# CPU.net
KiCad netlist of a schematic drawn in Altium Designer
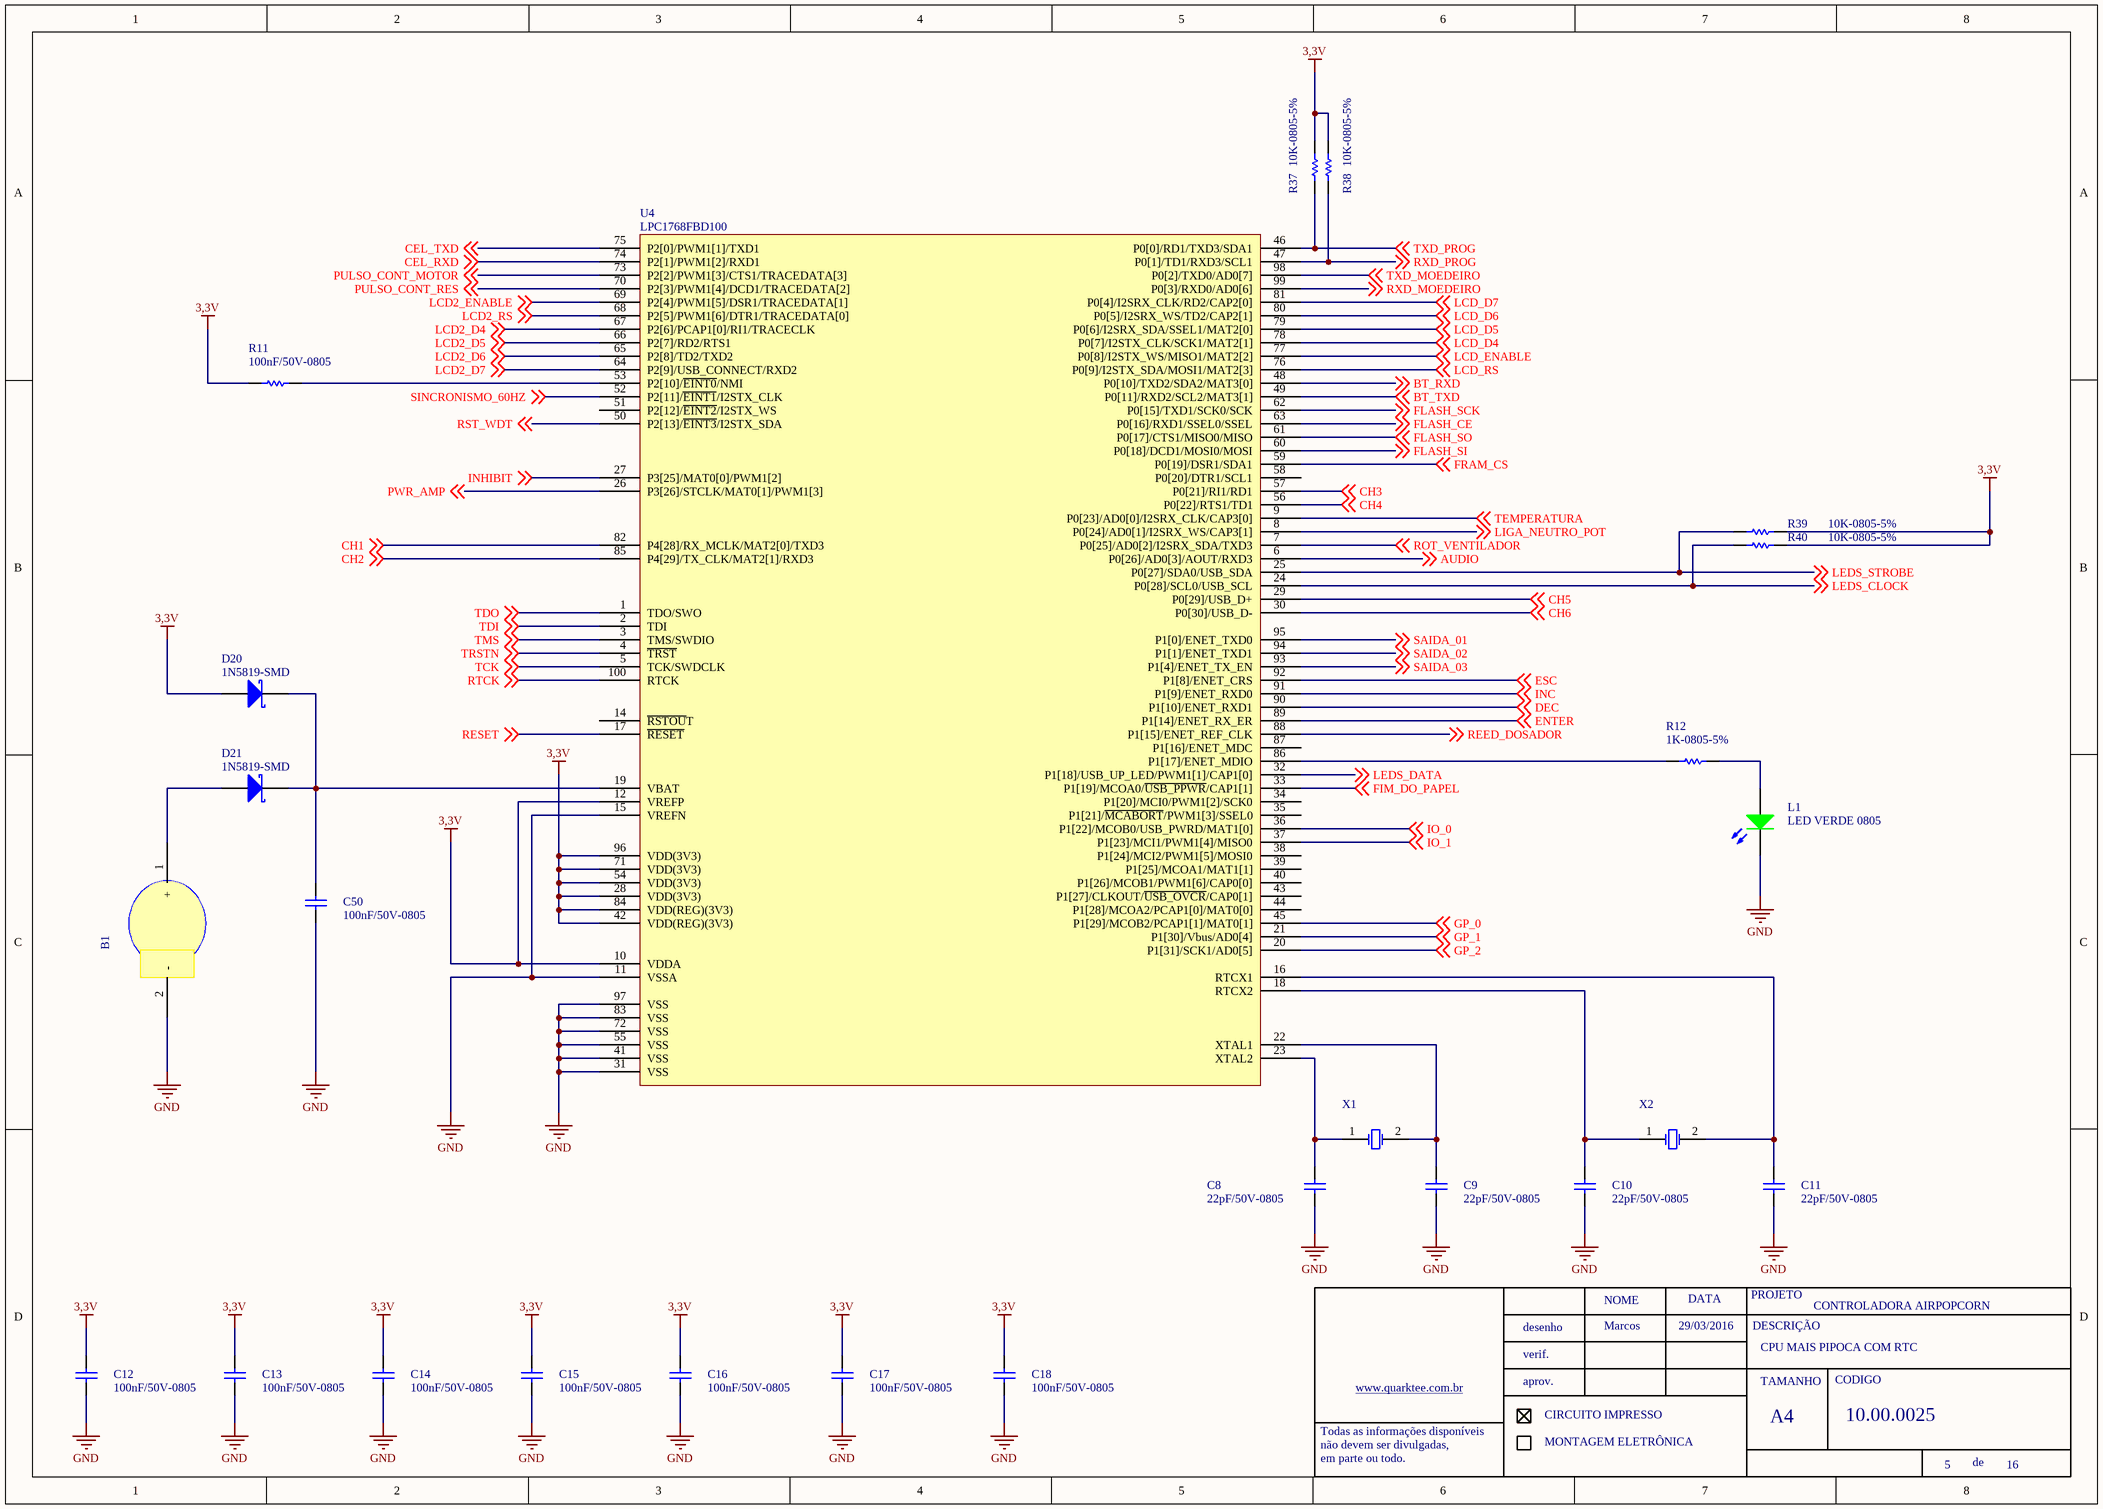
[diagram p0: CPU.SchDoc]

(export (version "E")
  (design (tool "Eeschema 10.0.6"))
  (components
    (comp (ref "B1")
      (value "~")
      (description "SUPORTE PILHA CR2032")
      (libsource (lib "ChaveDigital3") (part "SUPORTE PILHA CR2032"))
    )
    (comp (ref "C8")
      (value "22pF/50V-0805")
      (footprint "0805-REVISADO O")
      (description "22pF-0805-NPO")
      (libsource (lib "AquinoLib") (part "22pF-0805-NPO"))
    )
    (comp (ref "C9")
      (value "22pF/50V-0805")
      (footprint "0805-REVISADO O")
      (description "22pF-0805-NPO")
      (libsource (lib "AquinoLib") (part "22pF-0805-NPO"))
    )
    (comp (ref "C10")
      (value "22pF/50V-0805")
      (footprint "0805-REVISADO O")
      (description "22pF-0805-NPO")
      (libsource (lib "AquinoLib") (part "22pF-0805-NPO"))
    )
    (comp (ref "C11")
      (value "22pF/50V-0805")
      (footprint "0805-REVISADO O")
      (description "22pF-0805-NPO")
      (libsource (lib "AquinoLib") (part "22pF-0805-NPO"))
    )
    (comp (ref "C12")
      (value "100nF/50V-0805")
      (footprint "0805-REVISADO O")
      (description "100nF/50-0805-NPO")
      (libsource (lib "AquinoLib") (part "100nF/50-0805-NPO"))
    )
    (comp (ref "C13")
      (value "100nF/50V-0805")
      (footprint "0805-REVISADO O")
      (description "100nF/50-0805-NPO")
      (libsource (lib "AquinoLib") (part "100nF/50-0805-NPO"))
    )
    (comp (ref "C14")
      (value "100nF/50V-0805")
      (footprint "0805-REVISADO O")
      (description "100nF/50-0805-NPO")
      (libsource (lib "AquinoLib") (part "100nF/50-0805-NPO"))
    )
    (comp (ref "C15")
      (value "100nF/50V-0805")
      (footprint "0805-REVISADO O")
      (description "100nF/50-0805-NPO")
      (libsource (lib "AquinoLib") (part "100nF/50-0805-NPO"))
    )
    (comp (ref "C16")
      (value "100nF/50V-0805")
      (footprint "0805-REVISADO O")
      (description "100nF/50-0805-NPO")
      (libsource (lib "AquinoLib") (part "100nF/50-0805-NPO"))
    )
    (comp (ref "C17")
      (value "100nF/50V-0805")
      (footprint "0805-REVISADO O")
      (description "100nF/50-0805-NPO")
      (libsource (lib "AquinoLib") (part "100nF/50-0805-NPO"))
    )
    (comp (ref "C18")
      (value "100nF/50V-0805")
      (footprint "0805-REVISADO O")
      (description "100nF/50-0805-NPO")
      (libsource (lib "AquinoLib") (part "100nF/50-0805-NPO"))
    )
    (comp (ref "C50")
      (value "100nF/50V-0805")
      (footprint "0805-REVISADO O")
      (description "100nF/50-0805-NPO")
      (libsource (lib "AquinoLib") (part "100nF/50-0805-NPO"))
    )
    (comp (ref "D20")
      (value "1N5819-SMD")
      (description "1N5819")
      (libsource (lib "ChaveDigital3") (part "1N5819"))
    )
    (comp (ref "D21")
      (value "1N5819-SMD")
      (description "1N5819")
      (libsource (lib "ChaveDigital3") (part "1N5819"))
    )
    (comp (ref "L1")
      (value "LED VERDE 0805")
      (footprint "LED 0805 - REVI")
      (description "LED VERDE 0603 VERDE")
      (libsource (lib "AquinoLib") (part "LED VERDE 0603 SMD"))
    )
    (comp (ref "R11")
      (value "100nF/50V-0805")
      (footprint "0805-REVISADO O")
      (description "10K-0805-5%")
      (libsource (lib "AquinoLib") (part "10K-0805-5%"))
    )
    (comp (ref "R12")
      (value "1K-0805-5%")
      (footprint "0805-REVISADO O")
      (libsource (lib "AquinoLib") (part "1K-0805-5%"))
    )
    (comp (ref "R37")
      (value "10K-0805-5%")
      (footprint "0805-REVISADO O")
      (libsource (lib "AquinoLib") (part "10K-0805-5%"))
    )
    (comp (ref "R38")
      (value "10K-0805-5%")
      (footprint "0805-REVISADO O")
      (libsource (lib "AquinoLib") (part "10K-0805-5%"))
    )
    (comp (ref "R39")
      (value "10K-0805-5%")
      (footprint "0805-REVISADO O")
      (libsource (lib "AquinoLib") (part "10K-0805-5%"))
    )
    (comp (ref "R40")
      (value "10K-0805-5%")
      (footprint "0805-REVISADO O")
      (libsource (lib "AquinoLib") (part "10K-0805-5%"))
    )
    (comp (ref "U4")
      (value "LPC1768FBD100")
      (footprint "LQFP-100 pasta")
      (libsource (lib "ChaveDigital3") (part "LPC1768FDB100"))
    )
    (comp (ref "X1")
      (value "~")
      (footprint "XTALV'")
      (description "12MHZ")
      (libsource (lib "AquinoLib") (part "CRISTAL 12MHZ"))
    )
    (comp (ref "X2")
      (value "~")
      (footprint "XTAL_32768'")
      (description "CRISTAL 32.768Hz")
      (libsource (lib "AquinoLib") (part "CRISTAL 32.768 Hz"))
    )
  )
  (nets
    (net (code "1") (name "3,3V") (class "Default")
      (node (ref "C12") (pin "2") (pinfunction "2_2") (pintype "passive"))
      (node (ref "C13") (pin "2") (pinfunction "2_2") (pintype "passive"))
      (node (ref "C14") (pin "2") (pinfunction "2_2") (pintype "passive"))
      (node (ref "C15") (pin "2") (pinfunction "2_2") (pintype "passive"))
      (node (ref "C16") (pin "2") (pinfunction "2_2") (pintype "passive"))
      (node (ref "C17") (pin "2") (pinfunction "2_2") (pintype "passive"))
      (node (ref "C18") (pin "2") (pinfunction "2_2") (pintype "passive"))
      (node (ref "D20") (pin "1") (pinfunction "A_1") (pintype "passive"))
      (node (ref "R11") (pin "1") (pinfunction "1_1") (pintype "passive"))
      (node (ref "R37") (pin "2") (pinfunction "2_2") (pintype "passive"))
      (node (ref "R38") (pin "2") (pinfunction "2_2") (pintype "passive"))
      (node (ref "R39") (pin "2") (pinfunction "2_2") (pintype "passive"))
      (node (ref "R40") (pin "2") (pinfunction "2_2") (pintype "passive"))
      (node (ref "U4") (pin "10") (pinfunction "VDDA_10") (pintype "passive"))
      (node (ref "U4") (pin "12") (pinfunction "VREFP_12") (pintype "passive"))
      (node (ref "U4") (pin "28") (pinfunction "VDD(3V3)_28") (pintype "passive"))
      (node (ref "U4") (pin "42") (pinfunction "VDD(REG)(3V3)_42") (pintype "passive"))
      (node (ref "U4") (pin "54") (pinfunction "VDD(3V3)_54") (pintype "passive"))
      (node (ref "U4") (pin "71") (pinfunction "VDD(3V3)_71") (pintype "passive"))
      (node (ref "U4") (pin "84") (pinfunction "VDD(REG)(3V3)_84") (pintype "passive"))
      (node (ref "U4") (pin "96") (pinfunction "VDD(3V3)_96") (pintype "passive"))
    )
    (net (code "2") (name "AUDIO") (class "Default")
      (node (ref "U4") (pin "6") (pinfunction "P0[26]/AD0[3]/AOUT/RXD3_6") (pintype "passive"))
    )
    (net (code "3") (name "BT_RXD") (class "Default")
      (node (ref "U4") (pin "48") (pinfunction "P0[10]/TXD2/SDA2/MAT3[0]_48") (pintype "passive"))
    )
    (net (code "4") (name "BT_TXD") (class "Default")
      (node (ref "U4") (pin "49") (pinfunction "P0[11]/RXD2/SCL2/MAT3[1]_49") (pintype "passive"))
    )
    (net (code "5") (name "CEL_RXD") (class "Default")
      (node (ref "U4") (pin "74") (pinfunction "P2[1]/PWM1[2]/RXD1_74") (pintype "passive"))
    )
    (net (code "6") (name "CEL_TXD") (class "Default")
      (node (ref "U4") (pin "75") (pinfunction "P2[0]/PWM1[1]/TXD1_75") (pintype "passive"))
    )
    (net (code "7") (name "CH1") (class "Default")
      (node (ref "U4") (pin "82") (pinfunction "P4[28]/RX_MCLK/MAT2[0]/TXD3_82") (pintype "passive"))
    )
    (net (code "8") (name "CH2") (class "Default")
      (node (ref "U4") (pin "85") (pinfunction "P4[29]/TX_CLK/MAT2[1]/RXD3_85") (pintype "passive"))
    )
    (net (code "9") (name "CH3") (class "Default")
      (node (ref "U4") (pin "57") (pinfunction "P0[21]/RI1/RD1_57") (pintype "passive"))
    )
    (net (code "10") (name "CH4") (class "Default")
      (node (ref "U4") (pin "56") (pinfunction "P0[22]/RTS1/TD1_56") (pintype "passive"))
    )
    (net (code "11") (name "CH5") (class "Default")
      (node (ref "U4") (pin "29") (pinfunction "P0[29]/USB_D+_29") (pintype "passive"))
    )
    (net (code "12") (name "CH6") (class "Default")
      (node (ref "U4") (pin "30") (pinfunction "P0[30]/USB_D-_30") (pintype "passive"))
    )
    (net (code "13") (name "DEC") (class "Default")
      (node (ref "U4") (pin "90") (pinfunction "P1[10]/ENET_RXD1_90") (pintype "passive"))
    )
    (net (code "14") (name "ENTER") (class "Default")
      (node (ref "U4") (pin "89") (pinfunction "P1[14]/ENET_RX_ER_89") (pintype "passive"))
    )
    (net (code "15") (name "ESC") (class "Default")
      (node (ref "U4") (pin "92") (pinfunction "P1[8]/ENET_CRS_92") (pintype "passive"))
    )
    (net (code "16") (name "FIM_DO_PAPEL") (class "Default")
      (node (ref "U4") (pin "33") (pinfunction "P1[19]/MCOA0/~{USB_PPWR}/CAP1[1]_33") (pintype "passive"))
    )
    (net (code "17") (name "FLASH_CE") (class "Default")
      (node (ref "U4") (pin "63") (pinfunction "P0[16]/RXD1/SSEL0/SSEL_63") (pintype "passive"))
    )
    (net (code "18") (name "FLASH_SCK") (class "Default")
      (node (ref "U4") (pin "62") (pinfunction "P0[15]/TXD1/SCK0/SCK_62") (pintype "passive"))
    )
    (net (code "19") (name "FLASH_SI") (class "Default")
      (node (ref "U4") (pin "60") (pinfunction "P0[18]/DCD1/MOSI0/MOSI_60") (pintype "passive"))
    )
    (net (code "20") (name "FLASH_SO") (class "Default")
      (node (ref "U4") (pin "61") (pinfunction "P0[17]/CTS1/MISO0/MISO_61") (pintype "passive"))
    )
    (net (code "21") (name "FRAM_CS") (class "Default")
      (node (ref "U4") (pin "59") (pinfunction "P0[19]/DSR1/SDA1_59") (pintype "passive"))
    )
    (net (code "22") (name "GND") (class "Default")
      (node (ref "B1") (pin "2") (pinfunction "-_2") (pintype "passive"))
      (node (ref "C10") (pin "1") (pinfunction "1_1") (pintype "passive"))
      (node (ref "C11") (pin "1") (pinfunction "1_1") (pintype "passive"))
      (node (ref "C12") (pin "1") (pinfunction "1_1") (pintype "passive"))
      (node (ref "C13") (pin "1") (pinfunction "1_1") (pintype "passive"))
      (node (ref "C14") (pin "1") (pinfunction "1_1") (pintype "passive"))
      (node (ref "C15") (pin "1") (pinfunction "1_1") (pintype "passive"))
      (node (ref "C16") (pin "1") (pinfunction "1_1") (pintype "passive"))
      (node (ref "C17") (pin "1") (pinfunction "1_1") (pintype "passive"))
      (node (ref "C18") (pin "1") (pinfunction "1_1") (pintype "passive"))
      (node (ref "C50") (pin "1") (pinfunction "1_1") (pintype "passive"))
      (node (ref "C8") (pin "1") (pinfunction "1_1") (pintype "passive"))
      (node (ref "C9") (pin "1") (pinfunction "1_1") (pintype "passive"))
      (node (ref "L1") (pin "2") (pinfunction "K_2") (pintype "passive"))
      (node (ref "U4") (pin "11") (pinfunction "VSSA_11") (pintype "passive"))
      (node (ref "U4") (pin "15") (pinfunction "VREFN_15") (pintype "passive"))
      (node (ref "U4") (pin "31") (pinfunction "VSS_31") (pintype "passive"))
      (node (ref "U4") (pin "41") (pinfunction "VSS_41") (pintype "passive"))
      (node (ref "U4") (pin "55") (pinfunction "VSS_55") (pintype "passive"))
      (node (ref "U4") (pin "72") (pinfunction "VSS_72") (pintype "passive"))
      (node (ref "U4") (pin "83") (pinfunction "VSS_83") (pintype "passive"))
      (node (ref "U4") (pin "97") (pinfunction "VSS_97") (pintype "passive"))
    )
    (net (code "23") (name "GP_0") (class "Default")
      (node (ref "U4") (pin "45") (pinfunction "P1[29]/MCOB2/PCAP1[1]/MAT0[1]_45") (pintype "passive"))
    )
    (net (code "24") (name "GP_1") (class "Default")
      (node (ref "U4") (pin "21") (pinfunction "P1[30]/Vbus/AD0[4]_21") (pintype "passive"))
    )
    (net (code "25") (name "GP_2") (class "Default")
      (node (ref "U4") (pin "20") (pinfunction "P1[31]/SCK1/AD0[5]_20") (pintype "passive"))
    )
    (net (code "26") (name "INC") (class "Default")
      (node (ref "U4") (pin "91") (pinfunction "P1[9]/ENET_RXD0_91") (pintype "passive"))
    )
    (net (code "27") (name "INHIBIT") (class "Default")
      (node (ref "U4") (pin "27") (pinfunction "P3[25]/MAT0[0]/PWM1[2]_27") (pintype "passive"))
    )
    (net (code "28") (name "IO_0") (class "Default")
      (node (ref "U4") (pin "36") (pinfunction "P1[22]/MCOB0/USB_PWRD/MAT1[0]_36") (pintype "passive"))
    )
    (net (code "29") (name "IO_1") (class "Default")
      (node (ref "U4") (pin "37") (pinfunction "P1[23]/MCI1/PWM1[4]/MISO0_37") (pintype "passive"))
    )
    (net (code "30") (name "LCD2_D4") (class "Default")
      (node (ref "U4") (pin "67") (pinfunction "P2[6]/PCAP1[0]/RI1/TRACECLK_67") (pintype "passive"))
    )
    (net (code "31") (name "LCD2_D5") (class "Default")
      (node (ref "U4") (pin "66") (pinfunction "P2[7]/RD2/RTS1_66") (pintype "passive"))
    )
    (net (code "32") (name "LCD2_D6") (class "Default")
      (node (ref "U4") (pin "65") (pinfunction "P2[8]/TD2/TXD2_65") (pintype "passive"))
    )
    (net (code "33") (name "LCD2_D7") (class "Default")
      (node (ref "U4") (pin "64") (pinfunction "P2[9]/USB_CONNECT/RXD2_64") (pintype "passive"))
    )
    (net (code "34") (name "LCD2_ENABLE") (class "Default")
      (node (ref "U4") (pin "69") (pinfunction "P2[4]/PWM1[5]/DSR1/TRACEDATA[1]_69") (pintype "passive"))
    )
    (net (code "35") (name "LCD2_RS") (class "Default")
      (node (ref "U4") (pin "68") (pinfunction "P2[5]/PWM1[6]/DTR1/TRACEDATA[0]_68") (pintype "passive"))
    )
    (net (code "36") (name "LCD_D4") (class "Default")
      (node (ref "U4") (pin "78") (pinfunction "P0[7]/I2STX_CLK/SCK1/MAT2[1]_78") (pintype "passive"))
    )
    (net (code "37") (name "LCD_D5") (class "Default")
      (node (ref "U4") (pin "79") (pinfunction "P0[6]/I2SRX_SDA/SSEL1/MAT2[0]_79") (pintype "passive"))
    )
    (net (code "38") (name "LCD_D6") (class "Default")
      (node (ref "U4") (pin "80") (pinfunction "P0[5]/I2SRX_WS/TD2/CAP2[1]_80") (pintype "passive"))
    )
    (net (code "39") (name "LCD_D7") (class "Default")
      (node (ref "U4") (pin "81") (pinfunction "P0[4]/I2SRX_CLK/RD2/CAP2[0]_81") (pintype "passive"))
    )
    (net (code "40") (name "LCD_ENABLE") (class "Default")
      (node (ref "U4") (pin "77") (pinfunction "P0[8]/I2STX_WS/MISO1/MAT2[2]_77") (pintype "passive"))
    )
    (net (code "41") (name "LCD_RS") (class "Default")
      (node (ref "U4") (pin "76") (pinfunction "P0[9]/I2STX_SDA/MOSI1/MAT2[3]_76") (pintype "passive"))
    )
    (net (code "42") (name "LEDS_CLOCK") (class "Default")
      (node (ref "R40") (pin "1") (pinfunction "1_1") (pintype "passive"))
      (node (ref "U4") (pin "24") (pinfunction "P0[28]/SCL0/USB_SCL_24") (pintype "passive"))
    )
    (net (code "43") (name "LEDS_DATA") (class "Default")
      (node (ref "U4") (pin "32") (pinfunction "P1[18]/USB_UP_LED/PWM1[1]/CAP1[0]_32") (pintype "passive"))
    )
    (net (code "44") (name "LEDS_STROBE") (class "Default")
      (node (ref "R39") (pin "1") (pinfunction "1_1") (pintype "passive"))
      (node (ref "U4") (pin "25") (pinfunction "P0[27]/SDA0/USB_SDA_25") (pintype "passive"))
    )
    (net (code "45") (name "LIGA_NEUTRO_POT") (class "Default")
      (node (ref "U4") (pin "8") (pinfunction "P0[24]/AD0[1]/I2SRX_WS/CAP3[1]_8") (pintype "passive"))
    )
    (net (code "46") (name "Net-(B1-+)") (class "Default")
      (node (ref "B1") (pin "1") (pinfunction "+_1") (pintype "passive"))
      (node (ref "D21") (pin "1") (pinfunction "A_1") (pintype "passive"))
    )
    (net (code "47") (name "Net-(D20-K)") (class "Default")
      (node (ref "C50") (pin "2") (pinfunction "2_2") (pintype "passive"))
      (node (ref "D20") (pin "2") (pinfunction "K_2") (pintype "passive"))
      (node (ref "D21") (pin "2") (pinfunction "K_2") (pintype "passive"))
      (node (ref "U4") (pin "19") (pinfunction "VBAT_19") (pintype "passive"))
    )
    (net (code "48") (name "Net-(L1-A)") (class "Default")
      (node (ref "L1") (pin "1") (pinfunction "A_1") (pintype "passive"))
      (node (ref "R12") (pin "2") (pinfunction "2_2") (pintype "passive"))
    )
    (net (code "49") (name "Net-(U4-P1[17]{slash}ENET_MDIO)") (class "Default")
      (node (ref "R12") (pin "1") (pinfunction "1_1") (pintype "passive"))
      (node (ref "U4") (pin "86") (pinfunction "P1[17]/ENET_MDIO_86") (pintype "passive"))
    )
    (net (code "50") (name "Net-(U4-P2[10]{slash}~{EINT0}{slash}NMI)") (class "Default")
      (node (ref "R11") (pin "2") (pinfunction "2_2") (pintype "passive"))
      (node (ref "U4") (pin "53") (pinfunction "P2[10]/~{EINT0}/NMI_53") (pintype "passive"))
    )
    (net (code "51") (name "Net-(U4-RTCX1)") (class "Default")
      (node (ref "C11") (pin "2") (pinfunction "2_2") (pintype "passive"))
      (node (ref "U4") (pin "16") (pinfunction "RTCX1_16") (pintype "passive"))
      (node (ref "X2") (pin "2") (pinfunction "OSC2_2") (pintype "passive"))
    )
    (net (code "52") (name "Net-(U4-RTCX2)") (class "Default")
      (node (ref "C10") (pin "2") (pinfunction "2_2") (pintype "passive"))
      (node (ref "U4") (pin "18") (pinfunction "RTCX2_18") (pintype "passive"))
      (node (ref "X2") (pin "1") (pinfunction "OSC1_1") (pintype "passive"))
    )
    (net (code "53") (name "Net-(U4-XTAL1)") (class "Default")
      (node (ref "C9") (pin "2") (pinfunction "2_2") (pintype "passive"))
      (node (ref "U4") (pin "22") (pinfunction "XTAL1_22") (pintype "passive"))
      (node (ref "X1") (pin "2") (pinfunction "OSC2_2") (pintype "passive"))
    )
    (net (code "54") (name "Net-(U4-XTAL2)") (class "Default")
      (node (ref "C8") (pin "2") (pinfunction "2_2") (pintype "passive"))
      (node (ref "U4") (pin "23") (pinfunction "XTAL2_23") (pintype "passive"))
      (node (ref "X1") (pin "1") (pinfunction "OSC1_1") (pintype "passive"))
    )
    (net (code "55") (name "PULSO_CONT_MOTOR") (class "Default")
      (node (ref "U4") (pin "73") (pinfunction "P2[2]/PWM1[3]/CTS1/TRACEDATA[3]_73") (pintype "passive"))
    )
    (net (code "56") (name "PULSO_CONT_RES") (class "Default")
      (node (ref "U4") (pin "70") (pinfunction "P2[3]/PWM1[4]/DCD1/TRACEDATA[2]_70") (pintype "passive"))
    )
    (net (code "57") (name "PWR_AMP") (class "Default")
      (node (ref "U4") (pin "26") (pinfunction "P3[26]/STCLK/MAT0[1]/PWM1[3]_26") (pintype "passive"))
    )
    (net (code "58") (name "REED_DOSADOR") (class "Default")
      (node (ref "U4") (pin "88") (pinfunction "P1[15]/ENET_REF_CLK_88") (pintype "passive"))
    )
    (net (code "59") (name "RESET") (class "Default")
      (node (ref "U4") (pin "17") (pinfunction "~{RESET}_17") (pintype "passive"))
    )
    (net (code "60") (name "ROT_VENTILADOR") (class "Default")
      (node (ref "U4") (pin "7") (pinfunction "P0[25]/AD0[2]/I2SRX_SDA/TXD3_7") (pintype "passive"))
    )
    (net (code "61") (name "RST_WDT") (class "Default")
      (node (ref "U4") (pin "50") (pinfunction "P2[13]/~{EINT3}/I2STX_SDA_50") (pintype "passive"))
    )
    (net (code "62") (name "RTCK") (class "Default")
      (node (ref "U4") (pin "100") (pinfunction "RTCK_100") (pintype "passive"))
    )
    (net (code "63") (name "RXD_MOEDEIRO") (class "Default")
      (node (ref "U4") (pin "99") (pinfunction "P0[3]/RXD0/AD0[6]_99") (pintype "passive"))
    )
    (net (code "64") (name "RXD_PROG") (class "Default")
      (node (ref "R38") (pin "1") (pinfunction "1_1") (pintype "passive"))
      (node (ref "U4") (pin "47") (pinfunction "P0[1]/TD1/RXD3/SCL1_47") (pintype "passive"))
    )
    (net (code "65") (name "SAIDA_01") (class "Default")
      (node (ref "U4") (pin "95") (pinfunction "P1[0]/ENET_TXD0_95") (pintype "passive"))
    )
    (net (code "66") (name "SAIDA_02") (class "Default")
      (node (ref "U4") (pin "94") (pinfunction "P1[1]/ENET_TXD1_94") (pintype "passive"))
    )
    (net (code "67") (name "SAIDA_03") (class "Default")
      (node (ref "U4") (pin "93") (pinfunction "P1[4]/ENET_TX_EN_93") (pintype "passive"))
    )
    (net (code "68") (name "SINCRONISMO_60HZ") (class "Default")
      (node (ref "U4") (pin "52") (pinfunction "P2[11]/~{EINT1}/I2STX_CLK_52") (pintype "passive"))
    )
    (net (code "69") (name "TCK") (class "Default")
      (node (ref "U4") (pin "5") (pinfunction "TCK/SWDCLK_5") (pintype "passive"))
    )
    (net (code "70") (name "TDI") (class "Default")
      (node (ref "U4") (pin "2") (pinfunction "TDI_2") (pintype "passive"))
    )
    (net (code "71") (name "TDO") (class "Default")
      (node (ref "U4") (pin "1") (pinfunction "TDO/SWO_1") (pintype "passive"))
    )
    (net (code "72") (name "TEMPERATURA") (class "Default")
      (node (ref "U4") (pin "9") (pinfunction "P0[23]/AD0[0]/I2SRX_CLK/CAP3[0]_9") (pintype "passive"))
    )
    (net (code "73") (name "TMS") (class "Default")
      (node (ref "U4") (pin "3") (pinfunction "TMS/SWDIO_3") (pintype "passive"))
    )
    (net (code "74") (name "TRSTN") (class "Default")
      (node (ref "U4") (pin "4") (pinfunction "~{TRST}_4") (pintype "passive"))
    )
    (net (code "75") (name "TXD_MOEDEIRO") (class "Default")
      (node (ref "U4") (pin "98") (pinfunction "P0[2]/TXD0/AD0[7]_98") (pintype "passive"))
    )
    (net (code "76") (name "TXD_PROG") (class "Default")
      (node (ref "R37") (pin "1") (pinfunction "1_1") (pintype "passive"))
      (node (ref "U4") (pin "46") (pinfunction "P0[0]/RD1/TXD3/SDA1_46") (pintype "passive"))
    )
    (net (code "77") (name "unconnected-(U4-P0[20]{slash}DTR1{slash}SCL1-Pad58)") (class "Default")
      (node (ref "U4") (pin "58") (pinfunction "P0[20]/DTR1/SCL1_58") (pintype "passive"))
    )
    (net (code "78") (name "unconnected-(U4-P1[16]{slash}ENET_MDC-Pad87)") (class "Default")
      (node (ref "U4") (pin "87") (pinfunction "P1[16]/ENET_MDC_87") (pintype "passive"))
    )
    (net (code "79") (name "unconnected-(U4-P1[20]{slash}MCI0{slash}PWM1[2]{slash}SCK0-Pad34)") (class "Default")
      (node (ref "U4") (pin "34") (pinfunction "P1[20]/MCI0/PWM1[2]/SCK0_34") (pintype "passive"))
    )
    (net (code "80") (name "unconnected-(U4-P1[21]{slash}~{MCABORT}{slash}PWM1[3]{slash}SSEL0-Pad35)") (class "Default")
      (node (ref "U4") (pin "35") (pinfunction "P1[21]/~{MCABORT}/PWM1[3]/SSEL0_35") (pintype "passive"))
    )
    (net (code "81") (name "unconnected-(U4-P1[24]{slash}MCI2{slash}PWM1[5]{slash}MOSI0-Pad38)") (class "Default")
      (node (ref "U4") (pin "38") (pinfunction "P1[24]/MCI2/PWM1[5]/MOSI0_38") (pintype "passive"))
    )
    (net (code "82") (name "unconnected-(U4-P1[25]{slash}MCOA1{slash}MAT1[1]-Pad39)") (class "Default")
      (node (ref "U4") (pin "39") (pinfunction "P1[25]/MCOA1/MAT1[1]_39") (pintype "passive"))
    )
    (net (code "83") (name "unconnected-(U4-P1[26]{slash}MCOB1{slash}PWM1[6]{slash}CAP0[0]-Pad40)") (class "Default")
      (node (ref "U4") (pin "40") (pinfunction "P1[26]/MCOB1/PWM1[6]/CAP0[0]_40") (pintype "passive"))
    )
    (net (code "84") (name "unconnected-(U4-P1[27]{slash}CLKOUT{slash}~{USB_OVCR}{slash}CAP0[1]-Pad43)") (class "Default")
      (node (ref "U4") (pin "43") (pinfunction "P1[27]/CLKOUT/~{USB_OVCR}/CAP0[1]_43") (pintype "passive"))
    )
    (net (code "85") (name "unconnected-(U4-P1[28]{slash}MCOA2{slash}PCAP1[0]{slash}MAT0[0]-Pad44)") (class "Default")
      (node (ref "U4") (pin "44") (pinfunction "P1[28]/MCOA2/PCAP1[0]/MAT0[0]_44") (pintype "passive"))
    )
    (net (code "86") (name "unconnected-(U4-P2[12]{slash}~{EINT2}{slash}I2STX_WS-Pad51)") (class "Default")
      (node (ref "U4") (pin "51") (pinfunction "P2[12]/~{EINT2}/I2STX_WS_51") (pintype "passive"))
    )
    (net (code "87") (name "unconnected-(U4-~{RSTOU}T-Pad14)") (class "Default")
      (node (ref "U4") (pin "14") (pinfunction "~{RSTOU}T_14") (pintype "passive"))
    )
  )
)
